# Power.net
KiCad netlist of a schematic drawn in Altium Designer
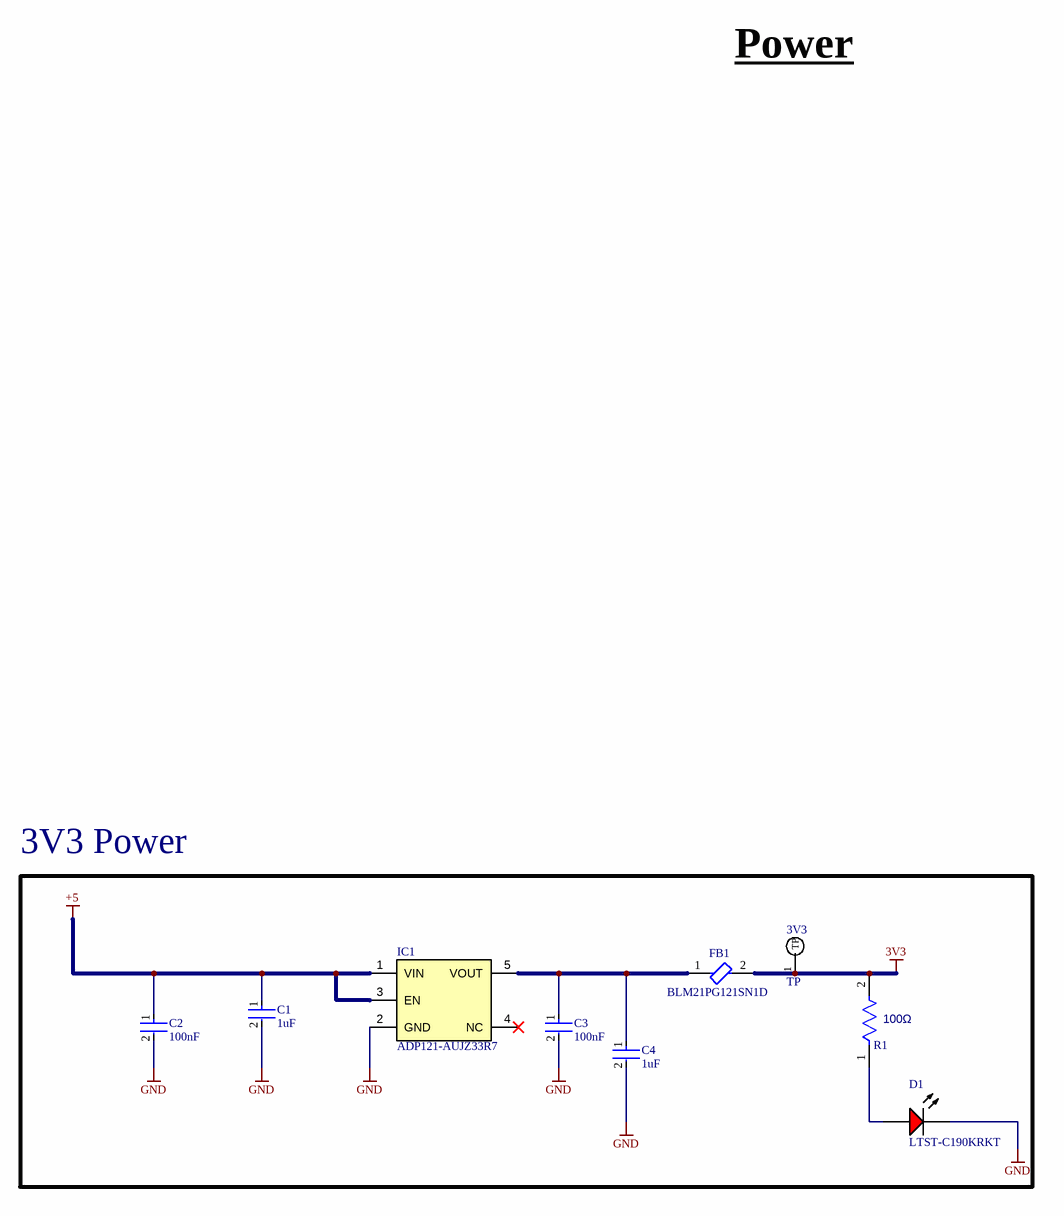
[diagram p0: Power.SchDoc]

(export (version "E")
  (design (tool "Eeschema 10.0.6"))
  (components
    (comp (ref "3V3")
      (value "TP")
      (footprint "TestPad")
      (libsource (lib "StrainComponents") (part "Test Points"))
    )
    (comp (ref "C1")
      (value "1uF")
      (footprint "FP-CC0603-DA-MFG")
      (description "CAP CER 1UF 16V X7R 0603")
      (fields (field (name "TOLERANCE") "0.1") (field (name "MANUFACTURER") "YAGEO"))
      (libsource (lib "Altium Content Vault") (part "11868f565c42a9108669ba33697ecf6"))
    )
    (comp (ref "C2")
      (value "100nF")
      (footprint "FP-GRM188-0_1-e0_2_0_55-IPC_A")
      (description "Chip Multilayer Ceramic Capacitors for General Purpose, 0603, 10uF, X5R, 15%, 20%, 6.3V")
      (fields (field (name "VOLTAGE") "6.3V") (field (name "TOLERANCE") "20%"))
      (libsource (lib "Altium Content Vault") (part "02cd4be3c70576c341d710602a673aa"))
    )
    (comp (ref "C3")
      (value "100nF")
      (footprint "FP-GRM188-0_1-e0_2_0_55-IPC_A")
      (description "Chip Multilayer Ceramic Capacitors for General Purpose, 0603, 10uF, X5R, 15%, 20%, 6.3V")
      (fields (field (name "VOLTAGE") "6.3V") (field (name "TOLERANCE") "20%"))
      (libsource (lib "Altium Content Vault") (part "02cd4be3c70576c341d710602a673aa"))
    )
    (comp (ref "C4")
      (value "1uF")
      (footprint "FP-CC0603-DA-MFG")
      (description "CAP CER 1UF 16V X7R 0603")
      (fields (field (name "TOLERANCE") "0.1") (field (name "MANUFACTURER") "YAGEO"))
      (libsource (lib "Altium Content Vault") (part "11868f565c42a9108669ba33697ecf6"))
    )
    (comp (ref "D1")
      (value "LTST-C190KRKT")
      (footprint "LTST-C191KRKT_V")
      (description "LED Uni-Color Red, 62.5 mW, 25 mA, -30 to 85 degC, 2-Pin SMD, RoHS, Tape and Reel")
      (fields (field (name "POWER") "75mW") (field (name "MANUFACTURER") "Lite-On"))
      (libsource (lib "Curtin Motorsport Team") (part "LED-RED-AK-2"))
    )
    (comp (ref "FB1")
      (value "BLM21PG121SN1D")
      (footprint "FP-BLM21-0_2-t0_85-e0_5-d-IPC_B")
      (description "Ferrite Beads Multi-Layer 120Ohm 25% 100MHz 3A 30mOhm DCR 0805 Paper T/R")
      (libsource (lib "Curtin Motorsport Team") (part "5f30dd21d616792df468990f7003faa"))
    )
    (comp (ref "IC1")
      (value "ADP121-AUJZ33R7")
      (footprint "SOT95P280X100-5N")
      (description "Integrated Circuit")
      (fields (field (name "MOUSER PART NUMBER") "584-ADP121-AUJZ33R7"))
      (libsource (lib "Curtin Motorsport Team") (part "ADP121-AUJZ33R7"))
    )
    (comp (ref "R1")
      (value "RC0603FR-07100RL")
      (footprint "FP-RC0603-0_55-IPC_A")
      (fields (field (name "TOLERANCE") "1%") (field (name "RESISTANCE") "100Ω"))
      (libsource (lib "Altium Content Vault") (part "1029c3af85768c4190bb7ad29bc67b5"))
    )
  )
  (nets
    (net (code "1") (name "+5") (class "Default")
      (node (ref "C1") (pin "1") (pinfunction "1_1") (pintype "passive"))
      (node (ref "C2") (pin "1") (pinfunction "1_1") (pintype "passive"))
      (node (ref "IC1") (pin "1") (pinfunction "VIN_1") (pintype "passive"))
      (node (ref "IC1") (pin "3") (pinfunction "EN_3") (pintype "passive"))
    )
    (net (code "2") (name "3V3") (class "Default")
      (node (ref "3V3") (pin "1") (pinfunction "TP_1") (pintype "passive"))
      (node (ref "FB1") (pin "2") (pinfunction "2_2") (pintype "passive"))
      (node (ref "R1") (pin "2") (pinfunction "2_2") (pintype "passive"))
    )
    (net (code "3") (name "GND") (class "Default")
      (node (ref "C1") (pin "2") (pinfunction "2_2") (pintype "passive"))
      (node (ref "C2") (pin "2") (pinfunction "2_2") (pintype "passive"))
      (node (ref "C3") (pin "2") (pinfunction "2_2") (pintype "passive"))
      (node (ref "C4") (pin "2") (pinfunction "2_2") (pintype "passive"))
      (node (ref "D1") (pin "2") (pinfunction "K_2") (pintype "passive"))
      (node (ref "IC1") (pin "2") (pinfunction "GND_2") (pintype "passive"))
    )
    (net (code "4") (name "Net-(D1-A)") (class "Default")
      (node (ref "D1") (pin "1") (pinfunction "A_1") (pintype "passive"))
      (node (ref "R1") (pin "1") (pinfunction "1_1") (pintype "passive"))
    )
    (net (code "5") (name "Net-(IC1-VOUT)") (class "Default")
      (node (ref "C3") (pin "1") (pinfunction "1_1") (pintype "passive"))
      (node (ref "C4") (pin "1") (pinfunction "1_1") (pintype "passive"))
      (node (ref "FB1") (pin "1") (pinfunction "1_1") (pintype "passive"))
      (node (ref "IC1") (pin "5") (pinfunction "VOUT_5") (pintype "passive"))
    )
    (net (code "6") (name "unconnected-(IC1-NC-Pad4)") (class "Default")
      (node (ref "IC1") (pin "4") (pinfunction "NC_4") (pintype "passive+no_connect"))
    )
  )
)
